# 4017-7Segment.net
KiCad netlist of a schematic drawn in EAGLE
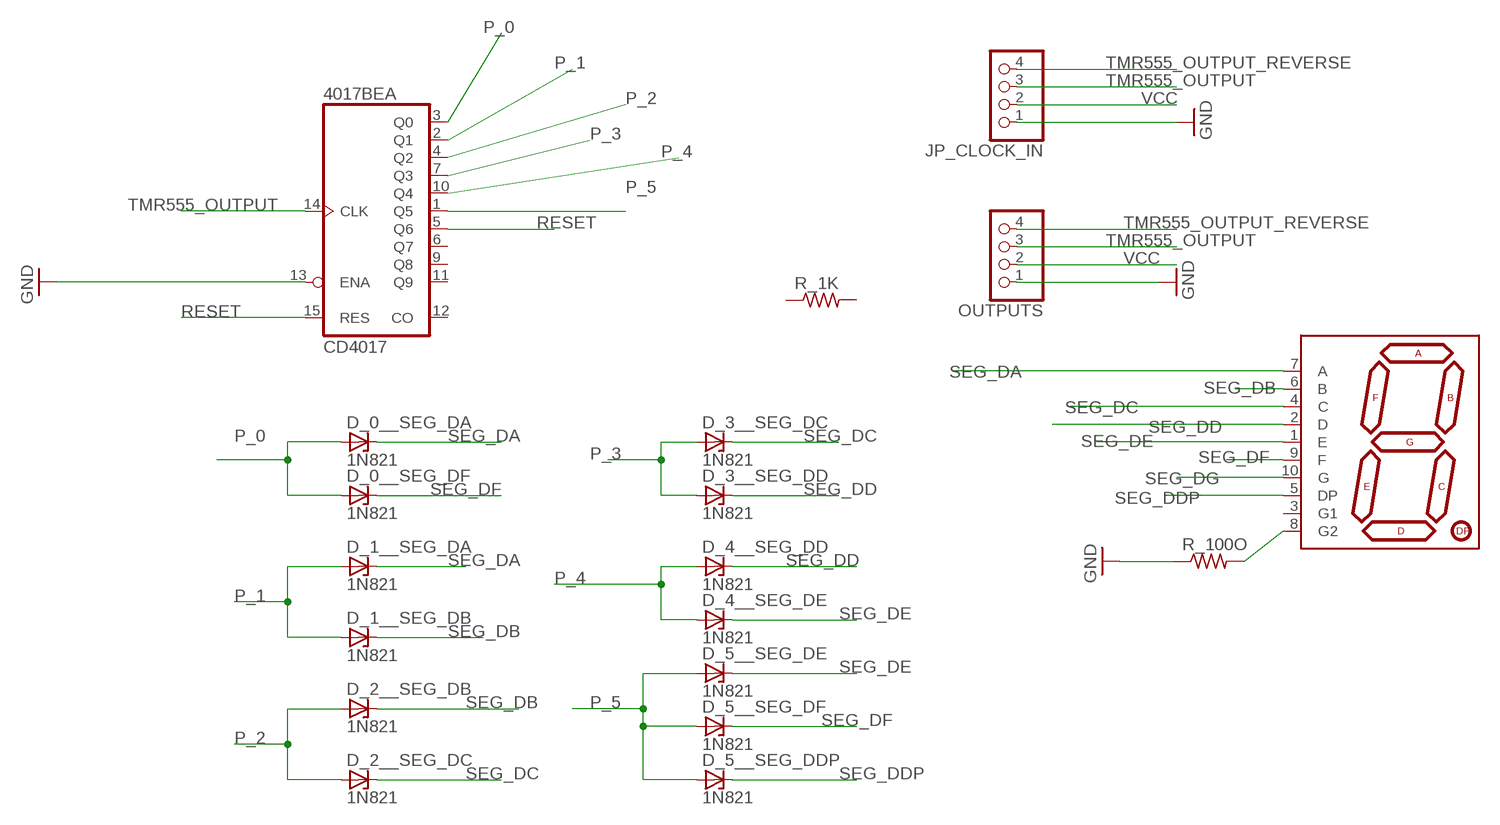
[diagram p0: schematic, sheet 1]

(export (version "E")
  (design (tool "Eeschema 10.0.6"))
  (components
    (comp (ref "4017BE")
      (value "CD4017")
      (footprint "eagle-import:DIL16")
      (libsource (lib "eagle-import") (part "CD4017"))
    )
    (comp (ref "D_0__SEG_DA")
      (value "1N821")
      (footprint "eagle-import:DO35Z10")
      (libsource (lib "eagle-import") (part "1N821"))
    )
    (comp (ref "D_0__SEG_DF")
      (value "1N821")
      (footprint "eagle-import:DO35Z10")
      (libsource (lib "eagle-import") (part "1N821"))
    )
    (comp (ref "D_1__SEG_DA")
      (value "1N821")
      (footprint "eagle-import:DO35Z10")
      (libsource (lib "eagle-import") (part "1N821"))
    )
    (comp (ref "D_1__SEG_DB")
      (value "1N821")
      (footprint "eagle-import:DO35Z10")
      (libsource (lib "eagle-import") (part "1N821"))
    )
    (comp (ref "D_2__SEG_DB")
      (value "1N821")
      (footprint "eagle-import:DO35Z10")
      (libsource (lib "eagle-import") (part "1N821"))
    )
    (comp (ref "D_2__SEG_DC")
      (value "1N821")
      (footprint "eagle-import:DO35Z10")
      (libsource (lib "eagle-import") (part "1N821"))
    )
    (comp (ref "D_3__SEG_DC")
      (value "1N821")
      (footprint "eagle-import:DO35Z10")
      (libsource (lib "eagle-import") (part "1N821"))
    )
    (comp (ref "D_3__SEG_DD")
      (value "1N821")
      (footprint "eagle-import:DO35Z10")
      (libsource (lib "eagle-import") (part "1N821"))
    )
    (comp (ref "D_4__SEG_DD")
      (value "1N821")
      (footprint "eagle-import:DO35Z10")
      (libsource (lib "eagle-import") (part "1N821"))
    )
    (comp (ref "D_4__SEG_DE")
      (value "1N821")
      (footprint "eagle-import:DO35Z10")
      (libsource (lib "eagle-import") (part "1N821"))
    )
    (comp (ref "D_5__SEG_DDP")
      (value "1N821")
      (footprint "eagle-import:DO35Z10")
      (libsource (lib "eagle-import") (part "1N821"))
    )
    (comp (ref "D_5__SEG_DE")
      (value "1N821")
      (footprint "eagle-import:DO35Z10")
      (libsource (lib "eagle-import") (part "1N821"))
    )
    (comp (ref "D_5__SEG_DF")
      (value "1N821")
      (footprint "eagle-import:DO35Z10")
      (libsource (lib "eagle-import") (part "1N821"))
    )
    (comp (ref "JP_CLOCK_IN")
      (value "PINHD-1X4")
      (footprint "eagle-import:1X04")
      (libsource (lib "eagle-import") (part "PINHD-1X4"))
    )
    (comp (ref "OUTPUTS")
      (value "PINHD-1X4")
      (footprint "eagle-import:1X04")
      (libsource (lib "eagle-import") (part "PINHD-1X4"))
    )
    (comp (ref "R_1K")
      (value "R-US_R1206")
      (footprint "eagle-import:R1206")
      (libsource (lib "eagle-import") (part "R-US_R1206"))
    )
    (comp (ref "R_100O")
      (value "R-US_R1206")
      (footprint "eagle-import:R1206")
      (libsource (lib "eagle-import") (part "R-US_R1206"))
    )
    (comp (ref "U$1")
      (value "7-SEGMENT-DISPLAYPTH")
      (footprint "eagle-import:7-SEGMENT-DISPLAY")
      (libsource (lib "eagle-import") (part "7-SEGMENT-DISPLAYPTH"))
    )
  )
  (nets
    (net (code "1") (name "/P_0") (class "Default")
      (node (ref "4017BE") (pin "3") (pinfunction "Q0_3") (pintype "output"))
      (node (ref "D_0__SEG_DA") (pin "A") (pinfunction "A_A") (pintype "passive"))
      (node (ref "D_0__SEG_DF") (pin "A") (pinfunction "A_A") (pintype "passive"))
    )
    (net (code "2") (name "/P_1") (class "Default")
      (node (ref "4017BE") (pin "2") (pinfunction "Q1_2") (pintype "output"))
      (node (ref "D_1__SEG_DA") (pin "A") (pinfunction "A_A") (pintype "passive"))
      (node (ref "D_1__SEG_DB") (pin "A") (pinfunction "A_A") (pintype "passive"))
    )
    (net (code "3") (name "/P_2") (class "Default")
      (node (ref "4017BE") (pin "4") (pinfunction "Q2_4") (pintype "output"))
      (node (ref "D_2__SEG_DB") (pin "A") (pinfunction "A_A") (pintype "passive"))
      (node (ref "D_2__SEG_DC") (pin "A") (pinfunction "A_A") (pintype "passive"))
    )
    (net (code "4") (name "/P_3") (class "Default")
      (node (ref "4017BE") (pin "7") (pinfunction "Q3_7") (pintype "output"))
      (node (ref "D_3__SEG_DC") (pin "A") (pinfunction "A_A") (pintype "passive"))
      (node (ref "D_3__SEG_DD") (pin "A") (pinfunction "A_A") (pintype "passive"))
    )
    (net (code "5") (name "/P_4") (class "Default")
      (node (ref "4017BE") (pin "10") (pinfunction "Q4_10") (pintype "output"))
      (node (ref "D_4__SEG_DD") (pin "A") (pinfunction "A_A") (pintype "passive"))
      (node (ref "D_4__SEG_DE") (pin "A") (pinfunction "A_A") (pintype "passive"))
    )
    (net (code "6") (name "/P_5") (class "Default")
      (node (ref "4017BE") (pin "1") (pinfunction "Q5_1") (pintype "output"))
      (node (ref "D_5__SEG_DDP") (pin "A") (pinfunction "A_A") (pintype "passive"))
      (node (ref "D_5__SEG_DE") (pin "A") (pinfunction "A_A") (pintype "passive"))
      (node (ref "D_5__SEG_DF") (pin "A") (pinfunction "A_A") (pintype "passive"))
    )
    (net (code "7") (name "/RESET") (class "Default")
      (node (ref "4017BE") (pin "15") (pinfunction "RES_15") (pintype "input"))
      (node (ref "4017BE") (pin "5") (pinfunction "Q6_5") (pintype "output"))
    )
    (net (code "8") (name "/SEG_DA") (class "Default")
      (node (ref "D_0__SEG_DA") (pin "C") (pinfunction "C_C") (pintype "passive"))
      (node (ref "D_1__SEG_DA") (pin "C") (pinfunction "C_C") (pintype "passive"))
      (node (ref "U$1") (pin "7") (pinfunction "A_7") (pintype "bidirectional"))
    )
    (net (code "9") (name "/SEG_DB") (class "Default")
      (node (ref "D_1__SEG_DB") (pin "C") (pinfunction "C_C") (pintype "passive"))
      (node (ref "D_2__SEG_DB") (pin "C") (pinfunction "C_C") (pintype "passive"))
      (node (ref "U$1") (pin "6") (pinfunction "B_6") (pintype "bidirectional"))
    )
    (net (code "10") (name "/SEG_DC") (class "Default")
      (node (ref "D_2__SEG_DC") (pin "C") (pinfunction "C_C") (pintype "passive"))
      (node (ref "D_3__SEG_DC") (pin "C") (pinfunction "C_C") (pintype "passive"))
      (node (ref "U$1") (pin "4") (pinfunction "C_4") (pintype "bidirectional"))
    )
    (net (code "11") (name "/SEG_DD") (class "Default")
      (node (ref "D_3__SEG_DD") (pin "C") (pinfunction "C_C") (pintype "passive"))
      (node (ref "D_4__SEG_DD") (pin "C") (pinfunction "C_C") (pintype "passive"))
      (node (ref "U$1") (pin "2") (pinfunction "D_2") (pintype "bidirectional"))
    )
    (net (code "12") (name "/SEG_DDP") (class "Default")
      (node (ref "D_5__SEG_DDP") (pin "C") (pinfunction "C_C") (pintype "passive"))
      (node (ref "U$1") (pin "5") (pinfunction "DP_5") (pintype "bidirectional"))
    )
    (net (code "13") (name "/SEG_DE") (class "Default")
      (node (ref "D_4__SEG_DE") (pin "C") (pinfunction "C_C") (pintype "passive"))
      (node (ref "D_5__SEG_DE") (pin "C") (pinfunction "C_C") (pintype "passive"))
      (node (ref "U$1") (pin "1") (pinfunction "E_1") (pintype "bidirectional"))
    )
    (net (code "14") (name "/SEG_DF") (class "Default")
      (node (ref "D_0__SEG_DF") (pin "C") (pinfunction "C_C") (pintype "passive"))
      (node (ref "D_5__SEG_DF") (pin "C") (pinfunction "C_C") (pintype "passive"))
      (node (ref "U$1") (pin "9") (pinfunction "F_9") (pintype "bidirectional"))
    )
    (net (code "15") (name "/SEG_DG") (class "Default")
      (node (ref "U$1") (pin "10") (pinfunction "G_10") (pintype "bidirectional"))
    )
    (net (code "16") (name "/TMR555_OUTPUT") (class "Default")
      (node (ref "4017BE") (pin "14") (pinfunction "CLK_14") (pintype "input"))
      (node (ref "JP_CLOCK_IN") (pin "3") (pinfunction "3_3") (pintype "passive"))
      (node (ref "OUTPUTS") (pin "3") (pinfunction "3_3") (pintype "passive"))
    )
    (net (code "17") (name "/TMR555_OUTPUT_REVERSE") (class "Default")
      (node (ref "JP_CLOCK_IN") (pin "4") (pinfunction "4_4") (pintype "passive"))
      (node (ref "OUTPUTS") (pin "4") (pinfunction "4_4") (pintype "passive"))
    )
    (net (code "18") (name "/VCC") (class "Default")
      (node (ref "JP_CLOCK_IN") (pin "2") (pinfunction "2_2") (pintype "passive"))
      (node (ref "OUTPUTS") (pin "2") (pinfunction "2_2") (pintype "passive"))
    )
    (net (code "19") (name "GND") (class "Default")
      (node (ref "4017BE") (pin "13") (pinfunction "ENA_13") (pintype "input"))
      (node (ref "JP_CLOCK_IN") (pin "1") (pinfunction "1_1") (pintype "passive"))
      (node (ref "OUTPUTS") (pin "1") (pinfunction "1_1") (pintype "passive"))
      (node (ref "R_100O") (pin "1") (pinfunction "1_1") (pintype "passive"))
    )
    (net (code "20") (name "Net-(U$1-G2)") (class "Default")
      (node (ref "R_100O") (pin "2") (pinfunction "2_2") (pintype "passive"))
      (node (ref "U$1") (pin "8") (pinfunction "G2_8") (pintype "bidirectional"))
    )
    (net (code "21") (name "unconnected-(4017BEA-CO-Pad12)") (class "Default")
      (node (ref "4017BE") (pin "12") (pinfunction "CO_12") (pintype "output"))
    )
    (net (code "22") (name "unconnected-(4017BEA-Q7-Pad6)") (class "Default")
      (node (ref "4017BE") (pin "6") (pinfunction "Q7_6") (pintype "output"))
    )
    (net (code "23") (name "unconnected-(4017BEA-Q8-Pad9)") (class "Default")
      (node (ref "4017BE") (pin "9") (pinfunction "Q8_9") (pintype "output"))
    )
    (net (code "24") (name "unconnected-(4017BEA-Q9-Pad11)") (class "Default")
      (node (ref "4017BE") (pin "11") (pinfunction "Q9_11") (pintype "output"))
    )
    (net (code "25") (name "unconnected-(R_1K-Pad1)") (class "Default")
      (node (ref "R_1K") (pin "1") (pinfunction "1_1") (pintype "passive"))
    )
    (net (code "26") (name "unconnected-(R_1K-Pad2)") (class "Default")
      (node (ref "R_1K") (pin "2") (pinfunction "2_2") (pintype "passive"))
    )
    (net (code "27") (name "unconnected-(U$1-G1-Pad3)") (class "Default")
      (node (ref "U$1") (pin "3") (pinfunction "G1_3") (pintype "bidirectional"))
    )
  )
)
